# control.net
KiCad netlist of a schematic drawn in EAGLE
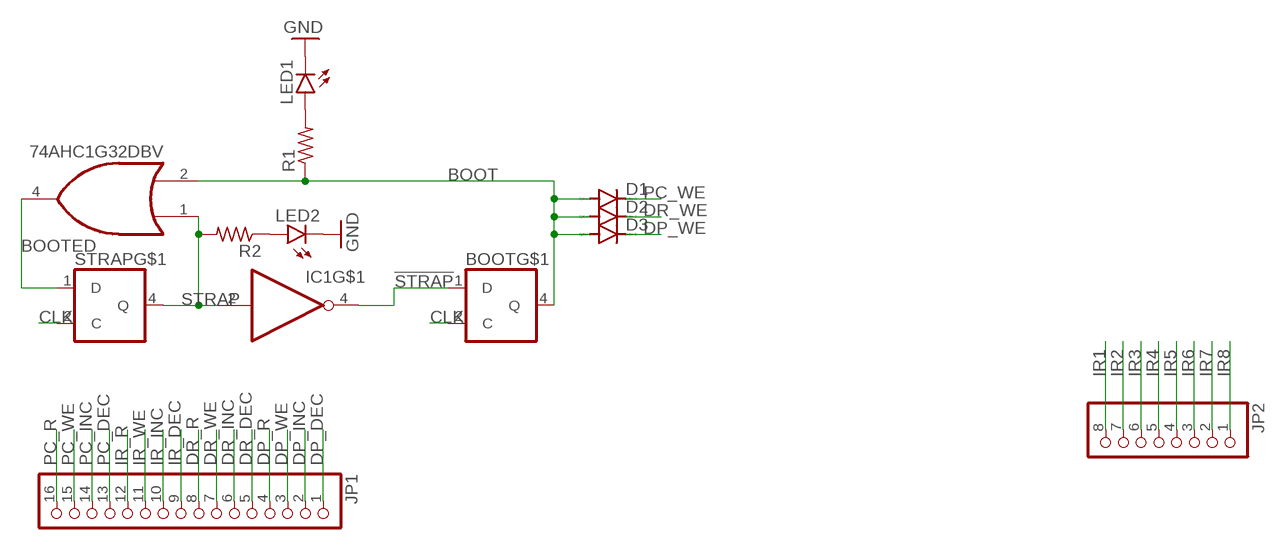
[diagram p0: schematic, sheet 1]

(export (version "E")
  (design (tool "Eeschema 10.0.6"))
  (components
    (comp (ref "BOOT")
      (value "74LVC1G79DBV")
      (footprint "eagle-import:SOT23-5")
      (libsource (lib "eagle-import") (part "741G79DBVLVC"))
    )
    (comp (ref "D1")
      (value "DIODE-SOD323-W")
      (footprint "eagle-import:SOD323-W")
      (libsource (lib "eagle-import") (part "DIODE-SOD323-W"))
    )
    (comp (ref "D2")
      (value "DIODE-SOD323-W")
      (footprint "eagle-import:SOD323-W")
      (libsource (lib "eagle-import") (part "DIODE-SOD323-W"))
    )
    (comp (ref "D3")
      (value "DIODE-SOD323-W")
      (footprint "eagle-import:SOD323-W")
      (libsource (lib "eagle-import") (part "DIODE-SOD323-W"))
    )
    (comp (ref "IC1")
      (value "74AUC1G06DBV")
      (footprint "eagle-import:SOT23-5")
      (libsource (lib "eagle-import") (part "741G06DBVAUC"))
    )
    (comp (ref "IC2")
      (value "74AHC1G32DBV")
      (footprint "eagle-import:SOT23-5")
      (libsource (lib "eagle-import") (part "741G32DBVAHC"))
    )
    (comp (ref "JP1")
      (value "PINHD-1X16")
      (footprint "eagle-import:1X16")
      (libsource (lib "eagle-import") (part "PINHD-1X16"))
    )
    (comp (ref "JP2")
      (value "PINHD-1X8")
      (footprint "eagle-import:1X08")
      (libsource (lib "eagle-import") (part "PINHD-1X8"))
    )
    (comp (ref "LED1")
      (value "LEDCHIP-LED0603")
      (footprint "eagle-import:CHIP-LED0603")
      (libsource (lib "eagle-import") (part "LEDCHIP-LED0603"))
    )
    (comp (ref "LED2")
      (value "LEDCHIP-LED0603")
      (footprint "eagle-import:CHIP-LED0603")
      (libsource (lib "eagle-import") (part "LEDCHIP-LED0603"))
    )
    (comp (ref "R1")
      (value "R-US_R0603")
      (footprint "eagle-import:R0603")
      (libsource (lib "eagle-import") (part "R-US_R0603"))
    )
    (comp (ref "R2")
      (value "R-US_R0603")
      (footprint "eagle-import:R0603")
      (libsource (lib "eagle-import") (part "R-US_R0603"))
    )
    (comp (ref "STRAP")
      (value "74LVC1G79DBV")
      (footprint "eagle-import:SOT23-5")
      (libsource (lib "eagle-import") (part "741G79DBVLVC"))
    )
  )
  (nets
    (net (code "1") (name "/BOOT") (class "Default")
      (node (ref "BOOT") (pin "4") (pinfunction "Q_4") (pintype "output"))
      (node (ref "D1") (pin "A") (pinfunction "A_A") (pintype "passive"))
      (node (ref "D2") (pin "A") (pinfunction "A_A") (pintype "passive"))
      (node (ref "D3") (pin "A") (pinfunction "A_A") (pintype "passive"))
      (node (ref "IC2") (pin "2") (pinfunction "I1_2") (pintype "input"))
      (node (ref "R1") (pin "1") (pinfunction "1_1") (pintype "passive"))
    )
    (net (code "2") (name "/BOOTED") (class "Default")
      (node (ref "IC2") (pin "4") (pinfunction "O_4") (pintype "output"))
      (node (ref "STRAP") (pin "1") (pinfunction "D_1") (pintype "input"))
    )
    (net (code "3") (name "/CLK") (class "Default")
      (node (ref "BOOT") (pin "2") (pinfunction "C_2") (pintype "input"))
      (node (ref "STRAP") (pin "2") (pinfunction "C_2") (pintype "input"))
    )
    (net (code "4") (name "/DP_DEC") (class "Default")
      (node (ref "JP1") (pin "1") (pinfunction "1_1") (pintype "passive"))
    )
    (net (code "5") (name "/DP_INC") (class "Default")
      (node (ref "JP1") (pin "2") (pinfunction "2_2") (pintype "passive"))
    )
    (net (code "6") (name "/DP_R") (class "Default")
      (node (ref "JP1") (pin "4") (pinfunction "4_4") (pintype "passive"))
    )
    (net (code "7") (name "/DP_WE") (class "Default")
      (node (ref "D3") (pin "C") (pinfunction "C_C") (pintype "passive"))
      (node (ref "JP1") (pin "3") (pinfunction "3_3") (pintype "passive"))
    )
    (net (code "8") (name "/DR_DEC") (class "Default")
      (node (ref "JP1") (pin "5") (pinfunction "5_5") (pintype "passive"))
    )
    (net (code "9") (name "/DR_INC") (class "Default")
      (node (ref "JP1") (pin "6") (pinfunction "6_6") (pintype "passive"))
    )
    (net (code "10") (name "/DR_R") (class "Default")
      (node (ref "JP1") (pin "8") (pinfunction "8_8") (pintype "passive"))
    )
    (net (code "11") (name "/DR_WE") (class "Default")
      (node (ref "D2") (pin "C") (pinfunction "C_C") (pintype "passive"))
      (node (ref "JP1") (pin "7") (pinfunction "7_7") (pintype "passive"))
    )
    (net (code "12") (name "/IR1") (class "Default")
      (node (ref "JP2") (pin "8") (pinfunction "8_8") (pintype "passive"))
    )
    (net (code "13") (name "/IR2") (class "Default")
      (node (ref "JP2") (pin "7") (pinfunction "7_7") (pintype "passive"))
    )
    (net (code "14") (name "/IR3") (class "Default")
      (node (ref "JP2") (pin "6") (pinfunction "6_6") (pintype "passive"))
    )
    (net (code "15") (name "/IR4") (class "Default")
      (node (ref "JP2") (pin "5") (pinfunction "5_5") (pintype "passive"))
    )
    (net (code "16") (name "/IR5") (class "Default")
      (node (ref "JP2") (pin "4") (pinfunction "4_4") (pintype "passive"))
    )
    (net (code "17") (name "/IR6") (class "Default")
      (node (ref "JP2") (pin "3") (pinfunction "3_3") (pintype "passive"))
    )
    (net (code "18") (name "/IR7") (class "Default")
      (node (ref "JP2") (pin "2") (pinfunction "2_2") (pintype "passive"))
    )
    (net (code "19") (name "/IR8") (class "Default")
      (node (ref "JP2") (pin "1") (pinfunction "1_1") (pintype "passive"))
    )
    (net (code "20") (name "/IR_DEC") (class "Default")
      (node (ref "JP1") (pin "9") (pinfunction "9_9") (pintype "passive"))
    )
    (net (code "21") (name "/IR_INC") (class "Default")
      (node (ref "JP1") (pin "10") (pinfunction "10_10") (pintype "passive"))
    )
    (net (code "22") (name "/IR_R") (class "Default")
      (node (ref "JP1") (pin "12") (pinfunction "12_12") (pintype "passive"))
    )
    (net (code "23") (name "/IR_WE") (class "Default")
      (node (ref "JP1") (pin "11") (pinfunction "11_11") (pintype "passive"))
    )
    (net (code "24") (name "/PC_DEC") (class "Default")
      (node (ref "JP1") (pin "13") (pinfunction "13_13") (pintype "passive"))
    )
    (net (code "25") (name "/PC_INC") (class "Default")
      (node (ref "JP1") (pin "14") (pinfunction "14_14") (pintype "passive"))
    )
    (net (code "26") (name "/PC_R") (class "Default")
      (node (ref "JP1") (pin "16") (pinfunction "16_16") (pintype "passive"))
    )
    (net (code "27") (name "/PC_WE") (class "Default")
      (node (ref "D1") (pin "C") (pinfunction "C_C") (pintype "passive"))
      (node (ref "JP1") (pin "15") (pinfunction "15_15") (pintype "passive"))
    )
    (net (code "28") (name "/STRAP") (class "Default")
      (node (ref "IC1") (pin "2") (pinfunction "I_2") (pintype "input"))
      (node (ref "IC2") (pin "1") (pinfunction "I0_1") (pintype "input"))
      (node (ref "R2") (pin "2") (pinfunction "2_2") (pintype "passive"))
      (node (ref "STRAP") (pin "4") (pinfunction "Q_4") (pintype "output"))
    )
    (net (code "29") (name "/~{STRAP}") (class "Default")
      (node (ref "BOOT") (pin "1") (pinfunction "D_1") (pintype "input"))
      (node (ref "IC1") (pin "4") (pinfunction "O_4") (pintype "open_collector"))
    )
    (net (code "30") (name "GND") (class "Default")
      (node (ref "LED1") (pin "C") (pinfunction "C_C") (pintype "passive"))
      (node (ref "LED2") (pin "C") (pinfunction "C_C") (pintype "passive"))
    )
    (net (code "31") (name "Net-(LED1-PadA)") (class "Default")
      (node (ref "LED1") (pin "A") (pinfunction "A_A") (pintype "passive"))
      (node (ref "R1") (pin "2") (pinfunction "2_2") (pintype "passive"))
    )
    (net (code "32") (name "Net-(LED2-PadA)") (class "Default")
      (node (ref "LED2") (pin "A") (pinfunction "A_A") (pintype "passive"))
      (node (ref "R2") (pin "1") (pinfunction "1_1") (pintype "passive"))
    )
  )
)
